# ASD2431.net
KiCad netlist of a schematic drawn in EAGLE
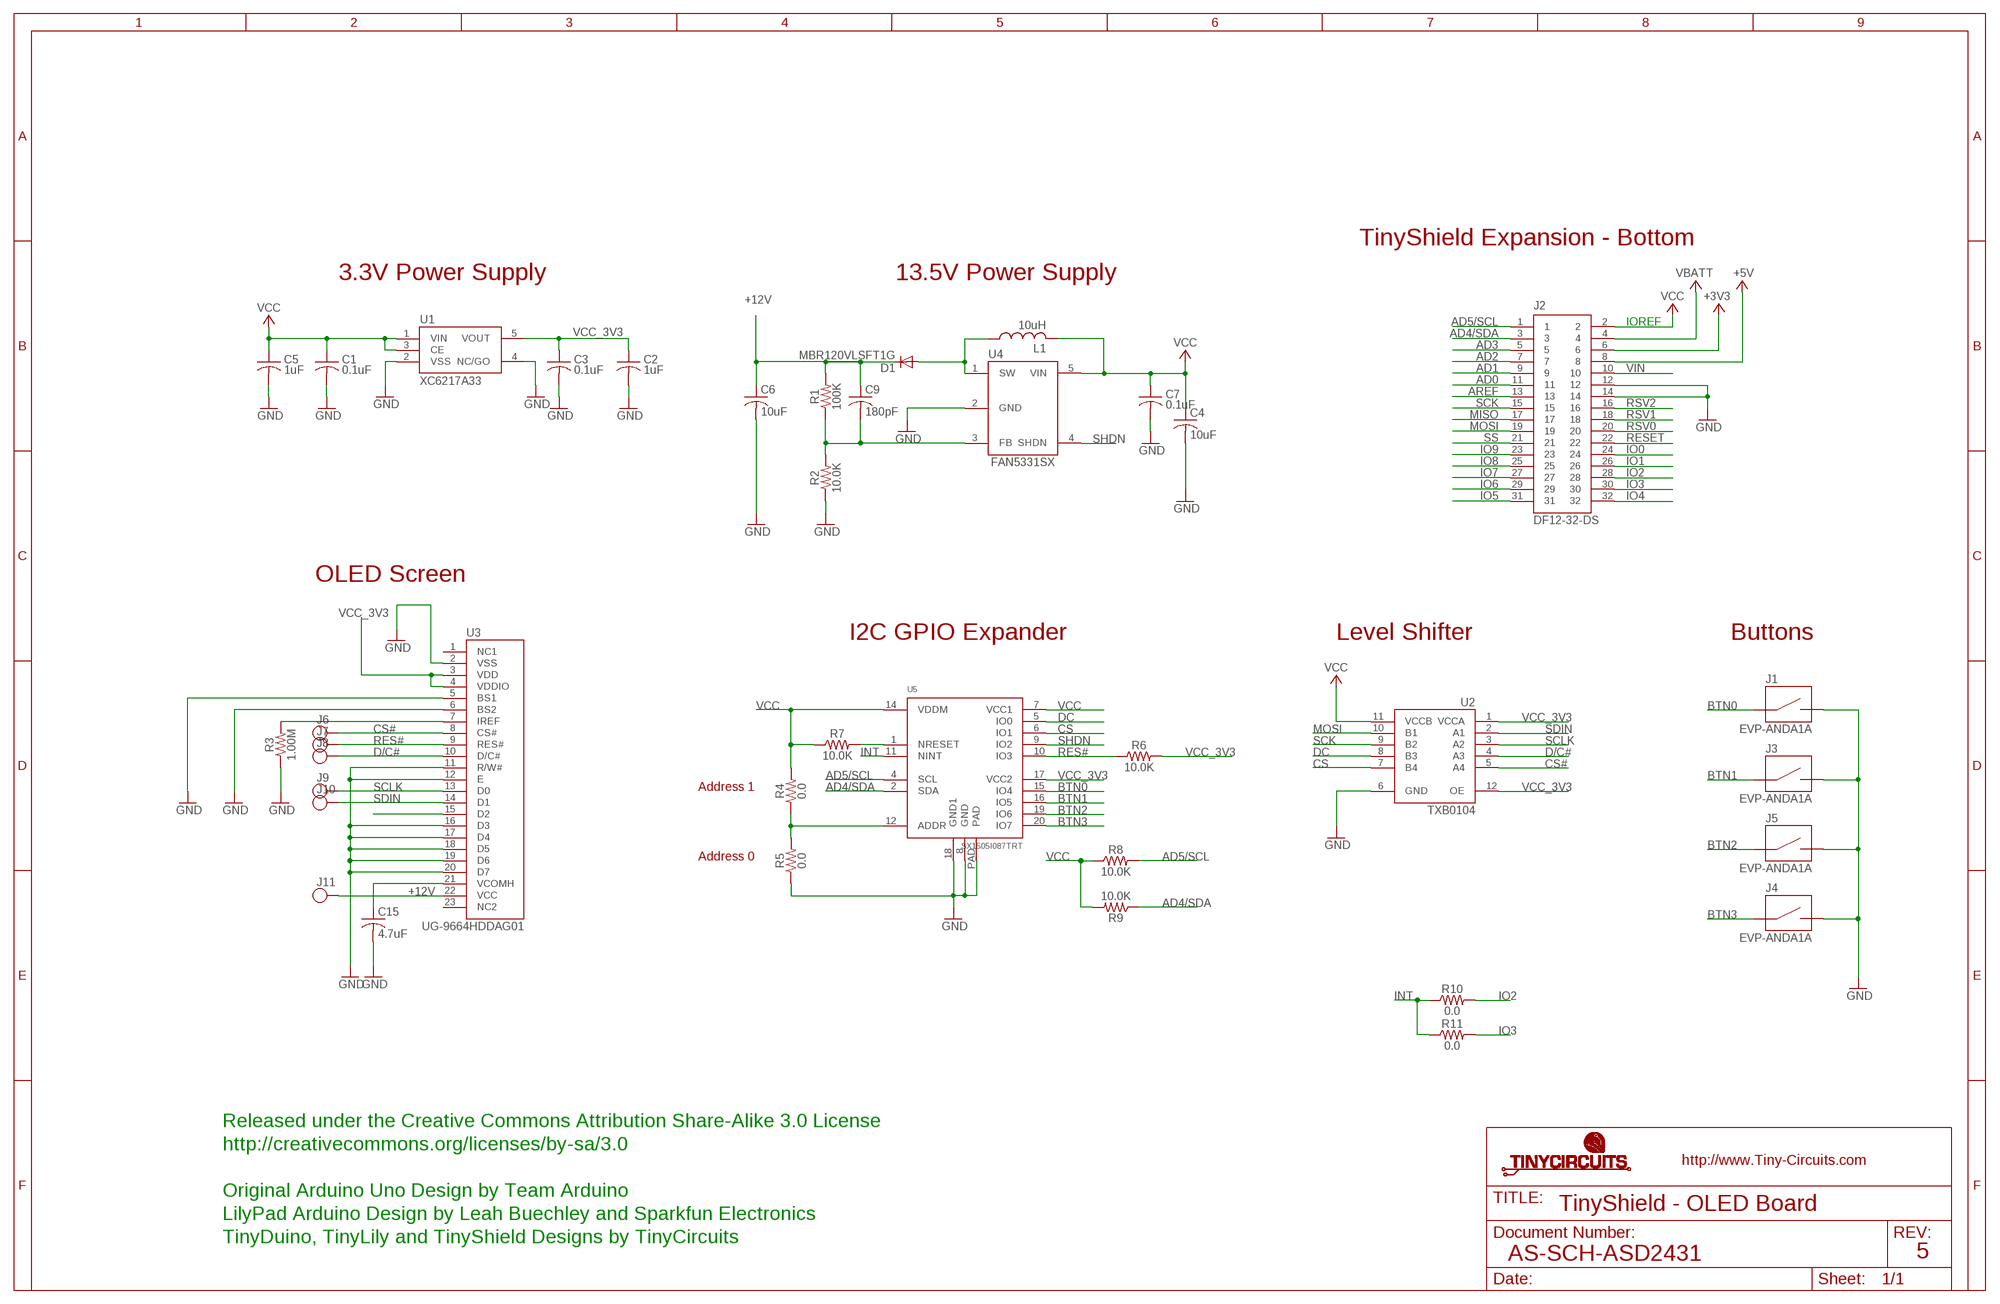
[diagram p0: schematic, sheet 1]

(export (version "E")
  (design (tool "Eeschema 10.0.6"))
  (components
    (comp (ref "C1")
      (value "0.1uF")
      (footprint "eagle-import:C0402")
      (fields (field (name "PARTNO") "AS-ITM-00008") (field (name "PARTNO_1") "AS-ITM-00008"))
      (libsource (lib "eagle-import") (part "AS-ITM-00008"))
    )
    (comp (ref "C2")
      (value "1uF")
      (footprint "eagle-import:C0402")
      (fields (field (name "PARTNO") "AS-ITM-00105") (field (name "PARTNO_1") "AS-ITM-00105"))
      (libsource (lib "eagle-import") (part "AS-ITM-00105"))
    )
    (comp (ref "C3")
      (value "0.1uF")
      (footprint "eagle-import:C0402")
      (fields (field (name "PARTNO") "AS-ITM-00008") (field (name "PARTNO_1") "AS-ITM-00008"))
      (libsource (lib "eagle-import") (part "AS-ITM-00008"))
    )
    (comp (ref "C4")
      (value "10uF")
      (footprint "eagle-import:C0805")
      (fields (field (name "PARTNO") "AS-ITM-00045") (field (name "PARTNO_1") "AS-ITM-00045"))
      (libsource (lib "eagle-import") (part "AS-ITM-00045"))
    )
    (comp (ref "C5")
      (value "1uF")
      (footprint "eagle-import:C0402")
      (fields (field (name "PARTNO") "AS-ITM-00105") (field (name "PARTNO_1") "AS-ITM-00105"))
      (libsource (lib "eagle-import") (part "AS-ITM-00105"))
    )
    (comp (ref "C6")
      (value "10uF")
      (footprint "eagle-import:C0805")
      (fields (field (name "PARTNO") "AS-ITM-00045") (field (name "PARTNO_1") "AS-ITM-00045"))
      (libsource (lib "eagle-import") (part "AS-ITM-00045"))
    )
    (comp (ref "C7")
      (value "0.1uF")
      (footprint "eagle-import:C0402")
      (fields (field (name "PARTNO") "AS-ITM-00008") (field (name "PARTNO_1") "AS-ITM-00008"))
      (libsource (lib "eagle-import") (part "AS-ITM-00008"))
    )
    (comp (ref "C9")
      (value "180pF")
      (footprint "eagle-import:0402")
      (fields (field (name "PARTNO") "AS-ITM-00243") (field (name "PARTNO_1") "AS-ITM-00243"))
      (libsource (lib "eagle-import") (part "AS-ITM-00243"))
    )
    (comp (ref "C15")
      (value "4.7uF")
      (footprint "eagle-import:1206_CAP_TANT")
      (fields (field (name "PARTNO") "AS-ITM-00232") (field (name "PARTNO_1") "AS-ITM-00232"))
      (libsource (lib "eagle-import") (part "AS-ITM-00232"))
    )
    (comp (ref "D1")
      (value "MBR120VLSFT1G")
      (footprint "eagle-import:SOD-123FL")
      (fields (field (name "PARTNO") "AS-ITM-00111"))
      (libsource (lib "eagle-import") (part "AS-ITM-00111"))
    )
    (comp (ref "J1")
      (value "EVP-ANDA1A")
      (footprint "eagle-import:PTS840GKP")
      (fields (field (name "PARTNO") "AS-ITM-00236") (field (name "PARTNO_1") "AS-ITM-00236"))
      (libsource (lib "eagle-import") (part "AS-ITM-00236"))
    )
    (comp (ref "J2")
      (value "DF12-32-DS")
      (footprint "eagle-import:DF12-32-DS")
      (fields (field (name "PARTNO") "AS-ITM-00012") (field (name "PARTNO_1") "AS-ITM-00012"))
      (libsource (lib "eagle-import") (part "AS-ITM-00012"))
    )
    (comp (ref "J3")
      (value "EVP-ANDA1A")
      (footprint "eagle-import:PTS840GKP")
      (fields (field (name "PARTNO") "AS-ITM-00236") (field (name "PARTNO_1") "AS-ITM-00236"))
      (libsource (lib "eagle-import") (part "AS-ITM-00236"))
    )
    (comp (ref "J4")
      (value "EVP-ANDA1A")
      (footprint "eagle-import:PTS840GKP")
      (fields (field (name "PARTNO") "AS-ITM-00236") (field (name "PARTNO_1") "AS-ITM-00236"))
      (libsource (lib "eagle-import") (part "AS-ITM-00236"))
    )
    (comp (ref "J5")
      (value "EVP-ANDA1A")
      (footprint "eagle-import:PTS840GKP")
      (fields (field (name "PARTNO") "AS-ITM-00236") (field (name "PARTNO_1") "AS-ITM-00236"))
      (libsource (lib "eagle-import") (part "AS-ITM-00236"))
    )
    (comp (ref "J6")
      (value "TEST_POINT")
      (footprint "eagle-import:TEST_POINT_1MM")
      (libsource (lib "eagle-import") (part "TEST_POINT"))
    )
    (comp (ref "J7")
      (value "TEST_POINT")
      (footprint "eagle-import:TEST_POINT_1MM")
      (libsource (lib "eagle-import") (part "TEST_POINT"))
    )
    (comp (ref "J8")
      (value "TEST_POINT")
      (footprint "eagle-import:TEST_POINT_1MM")
      (libsource (lib "eagle-import") (part "TEST_POINT"))
    )
    (comp (ref "J9")
      (value "TEST_POINT")
      (footprint "eagle-import:TEST_POINT_1MM")
      (libsource (lib "eagle-import") (part "TEST_POINT"))
    )
    (comp (ref "J10")
      (value "TEST_POINT")
      (footprint "eagle-import:TEST_POINT_1MM")
      (libsource (lib "eagle-import") (part "TEST_POINT"))
    )
    (comp (ref "J11")
      (value "TEST_POINT")
      (footprint "eagle-import:TEST_POINT_1MM")
      (libsource (lib "eagle-import") (part "TEST_POINT"))
    )
    (comp (ref "L1")
      (value "10uH")
      (footprint "eagle-import:R0805")
      (fields (field (name "PARTNO") "AS-ITM-00165"))
      (libsource (lib "eagle-import") (part "AS-ITM-00165"))
    )
    (comp (ref "R1")
      (value "100K")
      (footprint "eagle-import:0402")
      (fields (field (name "PARTNO") "AS-ITM-00004"))
      (libsource (lib "eagle-import") (part "AS-ITM-00004"))
    )
    (comp (ref "R2")
      (value "10.0K")
      (footprint "eagle-import:0402")
      (fields (field (name "PARTNO") "AS-ITM-00032"))
      (libsource (lib "eagle-import") (part "AS-ITM-00032"))
    )
    (comp (ref "R3")
      (value "1.00M")
      (footprint "eagle-import:0402")
      (fields (field (name "PARTNO") "AS-ITM-00005"))
      (libsource (lib "eagle-import") (part "AS-ITM-00005"))
    )
    (comp (ref "R4")
      (value "0.0")
      (footprint "eagle-import:0402")
      (fields (field (name "PARTNO") "AS-ITM-00076"))
      (libsource (lib "eagle-import") (part "AS-ITM-00076"))
    )
    (comp (ref "R5")
      (value "0.0")
      (footprint "eagle-import:0402")
      (fields (field (name "PARTNO") "AS-ITM-00076"))
      (libsource (lib "eagle-import") (part "AS-ITM-00076"))
    )
    (comp (ref "R6")
      (value "10.0K")
      (footprint "eagle-import:0402")
      (fields (field (name "PARTNO") "AS-ITM-00032"))
      (libsource (lib "eagle-import") (part "AS-ITM-00032"))
    )
    (comp (ref "R7")
      (value "10.0K")
      (footprint "eagle-import:0402")
      (fields (field (name "PARTNO") "AS-ITM-00032") (field (name "PARTNO_1") "AS-ITM-00032"))
      (libsource (lib "eagle-import") (part "AS-ITM-00032"))
    )
    (comp (ref "R8")
      (value "10.0K")
      (footprint "eagle-import:0402")
      (fields (field (name "PARTNO") "AS-ITM-00032") (field (name "PARTNO_1") "AS-ITM-00032"))
      (libsource (lib "eagle-import") (part "AS-ITM-00032"))
    )
    (comp (ref "R9")
      (value "10.0K")
      (footprint "eagle-import:0402")
      (fields (field (name "PARTNO") "AS-ITM-00032") (field (name "PARTNO_1") "AS-ITM-00032"))
      (libsource (lib "eagle-import") (part "AS-ITM-00032"))
    )
    (comp (ref "R10")
      (value "0.0")
      (footprint "eagle-import:0402")
      (fields (field (name "PARTNO") "AS-ITM-00076") (field (name "PARTNO_1") "AS-ITM-00076"))
      (libsource (lib "eagle-import") (part "AS-ITM-00076"))
    )
    (comp (ref "R11")
      (value "0.0")
      (footprint "eagle-import:0402")
      (fields (field (name "PARTNO") "AS-ITM-00076") (field (name "PARTNO_1") "AS-ITM-00076"))
      (libsource (lib "eagle-import") (part "AS-ITM-00076"))
    )
    (comp (ref "U1")
      (value "XC6217A33")
      (footprint "eagle-import:SOT-25")
      (fields (field (name "PARTNO") "AS-ITM-00249") (field (name "PARTNO_1") "AS-ITM-00249"))
      (libsource (lib "eagle-import") (part "AS-ITM-00249"))
    )
    (comp (ref "U2")
      (value "TXB0104")
      (footprint "eagle-import:UQFN-12")
      (fields (field (name "PARTNO") "AS-ITM-00048"))
      (libsource (lib "eagle-import") (part "AS-ITM-00048"))
    )
    (comp (ref "U3")
      (value "UG-9664HDDAG01")
      (footprint "eagle-import:OLED_DISPLAY")
      (fields (field (name "PARTNO") "AS-ITM-00158"))
      (libsource (lib "eagle-import") (part "AS-ITM-00158"))
    )
    (comp (ref "U4")
      (value "FAN5331SX")
      (footprint "eagle-import:SOT-23")
      (fields (field (name "PARTNO") "AS-ITM-00163"))
      (libsource (lib "eagle-import") (part "AS-ITM-00163"))
    )
    (comp (ref "U5")
      (value "SX1505I087TRT")
      (footprint "eagle-import:QFN-UT20")
      (fields (field (name "PARTNO") "AS-ITM-00203"))
      (libsource (lib "eagle-import") (part "AS-ITM-00203"))
    )
  )
  (nets
    (net (code "1") (name "+3V3") (class "Default")
      (node (ref "J2") (pin "6") (pinfunction "6_6") (pintype "bidirectional"))
    )
    (net (code "2") (name "+5V") (class "Default")
      (node (ref "J2") (pin "8") (pinfunction "8_8") (pintype "bidirectional"))
    )
    (net (code "3") (name "/+12V") (class "Default")
      (node (ref "C6") (pin "1") (pinfunction "1_1") (pintype "passive"))
      (node (ref "C9") (pin "1") (pinfunction "1_1") (pintype "passive"))
      (node (ref "D1") (pin "C") (pinfunction "C_C") (pintype "passive"))
      (node (ref "J11") (pin "P$1") (pinfunction "1_P$1") (pintype "bidirectional"))
      (node (ref "R1") (pin "2") (pinfunction "2_2") (pintype "passive"))
      (node (ref "U3") (pin "22") (pinfunction "VCC_22") (pintype "bidirectional"))
    )
    (net (code "4") (name "/AD0") (class "Default")
      (node (ref "J2") (pin "11") (pinfunction "11_11") (pintype "bidirectional"))
    )
    (net (code "5") (name "/AD1") (class "Default")
      (node (ref "J2") (pin "9") (pinfunction "9_9") (pintype "bidirectional"))
    )
    (net (code "6") (name "/AD2") (class "Default")
      (node (ref "J2") (pin "7") (pinfunction "7_7") (pintype "bidirectional"))
    )
    (net (code "7") (name "/AD3") (class "Default")
      (node (ref "J2") (pin "5") (pinfunction "5_5") (pintype "bidirectional"))
    )
    (net (code "8") (name "/AD4{slash}SDA") (class "Default")
      (node (ref "J2") (pin "3") (pinfunction "3_3") (pintype "bidirectional"))
      (node (ref "R9") (pin "1") (pinfunction "1_1") (pintype "passive"))
      (node (ref "U5") (pin "2") (pinfunction "SDA_2") (pintype "bidirectional"))
    )
    (net (code "9") (name "/AD5{slash}SCL") (class "Default")
      (node (ref "J2") (pin "1") (pinfunction "1_1") (pintype "bidirectional"))
      (node (ref "R8") (pin "2") (pinfunction "2_2") (pintype "passive"))
      (node (ref "U5") (pin "4") (pinfunction "SCL_4") (pintype "bidirectional"))
    )
    (net (code "10") (name "/AREF") (class "Default")
      (node (ref "J2") (pin "13") (pinfunction "13_13") (pintype "bidirectional"))
    )
    (net (code "11") (name "/BTN0") (class "Default")
      (node (ref "J1") (pin "1") (pinfunction "1_1") (pintype "bidirectional"))
      (node (ref "J1") (pin "2") (pinfunction "1_2") (pintype "bidirectional"))
      (node (ref "U5") (pin "15") (pinfunction "IO4_15") (pintype "bidirectional"))
    )
    (net (code "12") (name "/BTN1") (class "Default")
      (node (ref "J3") (pin "1") (pinfunction "1_1") (pintype "bidirectional"))
      (node (ref "J3") (pin "2") (pinfunction "1_2") (pintype "bidirectional"))
      (node (ref "U5") (pin "16") (pinfunction "IO5_16") (pintype "bidirectional"))
    )
    (net (code "13") (name "/BTN2") (class "Default")
      (node (ref "J5") (pin "1") (pinfunction "1_1") (pintype "bidirectional"))
      (node (ref "J5") (pin "2") (pinfunction "1_2") (pintype "bidirectional"))
      (node (ref "U5") (pin "19") (pinfunction "IO6_19") (pintype "bidirectional"))
    )
    (net (code "14") (name "/BTN3") (class "Default")
      (node (ref "J4") (pin "1") (pinfunction "1_1") (pintype "bidirectional"))
      (node (ref "J4") (pin "2") (pinfunction "1_2") (pintype "bidirectional"))
      (node (ref "U5") (pin "20") (pinfunction "IO7_20") (pintype "bidirectional"))
    )
    (net (code "15") (name "/CS") (class "Default")
      (node (ref "U2") (pin "7") (pinfunction "B4_7") (pintype "bidirectional"))
      (node (ref "U5") (pin "6") (pinfunction "IO1_6") (pintype "bidirectional"))
    )
    (net (code "16") (name "/CS#") (class "Default")
      (node (ref "J6") (pin "P$1") (pinfunction "1_P$1") (pintype "bidirectional"))
      (node (ref "U2") (pin "5") (pinfunction "A4_5") (pintype "bidirectional"))
      (node (ref "U3") (pin "8") (pinfunction "CS#_8") (pintype "bidirectional"))
    )
    (net (code "17") (name "/DC") (class "Default")
      (node (ref "U2") (pin "8") (pinfunction "B3_8") (pintype "bidirectional"))
      (node (ref "U5") (pin "5") (pinfunction "IO0_5") (pintype "bidirectional"))
    )
    (net (code "18") (name "/D{slash}C#") (class "Default")
      (node (ref "J8") (pin "P$1") (pinfunction "1_P$1") (pintype "bidirectional"))
      (node (ref "U2") (pin "4") (pinfunction "A3_4") (pintype "bidirectional"))
      (node (ref "U3") (pin "10") (pinfunction "D/C#_10") (pintype "bidirectional"))
    )
    (net (code "19") (name "/INT") (class "Default")
      (node (ref "R10") (pin "1") (pinfunction "1_1") (pintype "passive"))
      (node (ref "R11") (pin "1") (pinfunction "1_1") (pintype "passive"))
      (node (ref "U5") (pin "11") (pinfunction "NINT_11") (pintype "bidirectional"))
    )
    (net (code "20") (name "/IO0") (class "Default")
      (node (ref "J2") (pin "24") (pinfunction "24_24") (pintype "bidirectional"))
    )
    (net (code "21") (name "/IO1") (class "Default")
      (node (ref "J2") (pin "26") (pinfunction "26_26") (pintype "bidirectional"))
    )
    (net (code "22") (name "/IO2") (class "Default")
      (node (ref "J2") (pin "28") (pinfunction "28_28") (pintype "bidirectional"))
      (node (ref "R10") (pin "2") (pinfunction "2_2") (pintype "passive"))
    )
    (net (code "23") (name "/IO3") (class "Default")
      (node (ref "J2") (pin "30") (pinfunction "30_30") (pintype "bidirectional"))
      (node (ref "R11") (pin "2") (pinfunction "2_2") (pintype "passive"))
    )
    (net (code "24") (name "/IO4") (class "Default")
      (node (ref "J2") (pin "32") (pinfunction "32_32") (pintype "bidirectional"))
    )
    (net (code "25") (name "/IO5") (class "Default")
      (node (ref "J2") (pin "31") (pinfunction "31_31") (pintype "bidirectional"))
    )
    (net (code "26") (name "/IO6") (class "Default")
      (node (ref "J2") (pin "29") (pinfunction "29_29") (pintype "bidirectional"))
    )
    (net (code "27") (name "/IO7") (class "Default")
      (node (ref "J2") (pin "27") (pinfunction "27_27") (pintype "bidirectional"))
    )
    (net (code "28") (name "/IO8") (class "Default")
      (node (ref "J2") (pin "25") (pinfunction "25_25") (pintype "bidirectional"))
    )
    (net (code "29") (name "/IO9") (class "Default")
      (node (ref "J2") (pin "23") (pinfunction "23_23") (pintype "bidirectional"))
    )
    (net (code "30") (name "/MISO") (class "Default")
      (node (ref "J2") (pin "17") (pinfunction "17_17") (pintype "bidirectional"))
    )
    (net (code "31") (name "/MOSI") (class "Default")
      (node (ref "J2") (pin "19") (pinfunction "19_19") (pintype "bidirectional"))
      (node (ref "U2") (pin "10") (pinfunction "B1_10") (pintype "bidirectional"))
    )
    (net (code "32") (name "/RES#") (class "Default")
      (node (ref "J7") (pin "P$1") (pinfunction "1_P$1") (pintype "bidirectional"))
      (node (ref "R6") (pin "1") (pinfunction "1_1") (pintype "passive"))
      (node (ref "U3") (pin "9") (pinfunction "RES#_9") (pintype "bidirectional"))
      (node (ref "U5") (pin "10") (pinfunction "IO3_10") (pintype "bidirectional"))
    )
    (net (code "33") (name "/RESET") (class "Default")
      (node (ref "J2") (pin "22") (pinfunction "22_22") (pintype "bidirectional"))
    )
    (net (code "34") (name "/RSV0") (class "Default")
      (node (ref "J2") (pin "20") (pinfunction "20_20") (pintype "bidirectional"))
    )
    (net (code "35") (name "/RSV1") (class "Default")
      (node (ref "J2") (pin "18") (pinfunction "18_18") (pintype "bidirectional"))
    )
    (net (code "36") (name "/RSV2") (class "Default")
      (node (ref "J2") (pin "16") (pinfunction "16_16") (pintype "bidirectional"))
    )
    (net (code "37") (name "/SCK") (class "Default")
      (node (ref "J2") (pin "15") (pinfunction "15_15") (pintype "bidirectional"))
      (node (ref "U2") (pin "9") (pinfunction "B2_9") (pintype "bidirectional"))
    )
    (net (code "38") (name "/SCLK") (class "Default")
      (node (ref "J9") (pin "P$1") (pinfunction "1_P$1") (pintype "bidirectional"))
      (node (ref "U2") (pin "3") (pinfunction "A2_3") (pintype "bidirectional"))
      (node (ref "U3") (pin "13") (pinfunction "D0_13") (pintype "bidirectional"))
    )
    (net (code "39") (name "/SDIN") (class "Default")
      (node (ref "J10") (pin "P$1") (pinfunction "1_P$1") (pintype "bidirectional"))
      (node (ref "U2") (pin "2") (pinfunction "A1_2") (pintype "bidirectional"))
      (node (ref "U3") (pin "14") (pinfunction "D1_14") (pintype "bidirectional"))
    )
    (net (code "40") (name "/SHDN") (class "Default")
      (node (ref "U4") (pin "4") (pinfunction "SHDN_4") (pintype "bidirectional"))
      (node (ref "U5") (pin "9") (pinfunction "IO2_9") (pintype "bidirectional"))
    )
    (net (code "41") (name "/SS") (class "Default")
      (node (ref "J2") (pin "21") (pinfunction "21_21") (pintype "bidirectional"))
    )
    (net (code "42") (name "/VCC_3V3") (class "Default")
      (node (ref "C2") (pin "1") (pinfunction "1_1") (pintype "passive"))
      (node (ref "C3") (pin "1") (pinfunction "1_1") (pintype "passive"))
      (node (ref "R6") (pin "2") (pinfunction "2_2") (pintype "passive"))
      (node (ref "U1") (pin "5") (pinfunction "VOUT_5") (pintype "bidirectional"))
      (node (ref "U2") (pin "1") (pinfunction "VCCA_1") (pintype "bidirectional"))
      (node (ref "U2") (pin "12") (pinfunction "OE_12") (pintype "bidirectional"))
      (node (ref "U3") (pin "3") (pinfunction "VDD_3") (pintype "bidirectional"))
      (node (ref "U3") (pin "4") (pinfunction "VDDIO_4") (pintype "bidirectional"))
      (node (ref "U5") (pin "17") (pinfunction "VCC2_17") (pintype "bidirectional"))
    )
    (net (code "43") (name "/VIN") (class "Default")
      (node (ref "J2") (pin "10") (pinfunction "10_10") (pintype "bidirectional"))
    )
    (net (code "44") (name "GND") (class "Default")
      (node (ref "C1") (pin "2") (pinfunction "2_2") (pintype "passive"))
      (node (ref "C15") (pin "2") (pinfunction "2_2") (pintype "passive"))
      (node (ref "C2") (pin "2") (pinfunction "2_2") (pintype "passive"))
      (node (ref "C3") (pin "2") (pinfunction "2_2") (pintype "passive"))
      (node (ref "C4") (pin "2") (pinfunction "2_2") (pintype "passive"))
      (node (ref "C5") (pin "2") (pinfunction "2_2") (pintype "passive"))
      (node (ref "C6") (pin "2") (pinfunction "2_2") (pintype "passive"))
      (node (ref "C7") (pin "2") (pinfunction "2_2") (pintype "passive"))
      (node (ref "J1") (pin "3") (pinfunction "2_3") (pintype "bidirectional"))
      (node (ref "J1") (pin "4") (pinfunction "2_4") (pintype "bidirectional"))
      (node (ref "J2") (pin "12") (pinfunction "12_12") (pintype "bidirectional"))
      (node (ref "J2") (pin "14") (pinfunction "14_14") (pintype "bidirectional"))
      (node (ref "J3") (pin "3") (pinfunction "2_3") (pintype "bidirectional"))
      (node (ref "J3") (pin "4") (pinfunction "2_4") (pintype "bidirectional"))
      (node (ref "J4") (pin "3") (pinfunction "2_3") (pintype "bidirectional"))
      (node (ref "J4") (pin "4") (pinfunction "2_4") (pintype "bidirectional"))
      (node (ref "J5") (pin "3") (pinfunction "2_3") (pintype "bidirectional"))
      (node (ref "J5") (pin "4") (pinfunction "2_4") (pintype "bidirectional"))
      (node (ref "R2") (pin "1") (pinfunction "1_1") (pintype "passive"))
      (node (ref "R3") (pin "1") (pinfunction "1_1") (pintype "passive"))
      (node (ref "R5") (pin "1") (pinfunction "1_1") (pintype "passive"))
      (node (ref "U1") (pin "2") (pinfunction "VSS_2") (pintype "power_in"))
      (node (ref "U1") (pin "4") (pinfunction "NC/GO_4") (pintype "bidirectional"))
      (node (ref "U2") (pin "6") (pinfunction "GND_6") (pintype "bidirectional"))
      (node (ref "U3") (pin "11") (pinfunction "R/W#_11") (pintype "bidirectional"))
      (node (ref "U3") (pin "12") (pinfunction "E_12") (pintype "bidirectional"))
      (node (ref "U3") (pin "16") (pinfunction "D3_16") (pintype "bidirectional"))
      (node (ref "U3") (pin "17") (pinfunction "D4_17") (pintype "bidirectional"))
      (node (ref "U3") (pin "18") (pinfunction "D5_18") (pintype "bidirectional"))
      (node (ref "U3") (pin "19") (pinfunction "D6_19") (pintype "bidirectional"))
      (node (ref "U3") (pin "2") (pinfunction "VSS_2") (pintype "bidirectional"))
      (node (ref "U3") (pin "20") (pinfunction "D7_20") (pintype "bidirectional"))
      (node (ref "U3") (pin "5") (pinfunction "BS1_5") (pintype "bidirectional"))
      (node (ref "U3") (pin "6") (pinfunction "BS2_6") (pintype "bidirectional"))
      (node (ref "U4") (pin "2") (pinfunction "GND_2") (pintype "bidirectional"))
      (node (ref "U5") (pin "18") (pinfunction "GND1_18") (pintype "bidirectional"))
      (node (ref "U5") (pin "8") (pinfunction "GND_8") (pintype "bidirectional"))
      (node (ref "U5") (pin "PAD") (pinfunction "PAD_PAD") (pintype "bidirectional"))
    )
    (net (code "45") (name "Net-(U3-IREF)") (class "Default")
      (node (ref "R3") (pin "2") (pinfunction "2_2") (pintype "passive"))
      (node (ref "U3") (pin "7") (pinfunction "IREF_7") (pintype "bidirectional"))
    )
    (net (code "46") (name "Net-(U3-VCOMH)") (class "Default")
      (node (ref "C15") (pin "1") (pinfunction "1_1") (pintype "passive"))
      (node (ref "U3") (pin "21") (pinfunction "VCOMH_21") (pintype "bidirectional"))
    )
    (net (code "47") (name "Net-(U4-FB)") (class "Default")
      (node (ref "C9") (pin "2") (pinfunction "2_2") (pintype "passive"))
      (node (ref "R1") (pin "1") (pinfunction "1_1") (pintype "passive"))
      (node (ref "R2") (pin "2") (pinfunction "2_2") (pintype "passive"))
      (node (ref "U4") (pin "3") (pinfunction "FB_3") (pintype "bidirectional"))
    )
    (net (code "48") (name "Net-(U4-SW)") (class "Default")
      (node (ref "D1") (pin "A") (pinfunction "A_A") (pintype "passive"))
      (node (ref "L1") (pin "1") (pinfunction "1_1") (pintype "passive"))
      (node (ref "U4") (pin "1") (pinfunction "SW_1") (pintype "bidirectional"))
    )
    (net (code "49") (name "Net-(U5-ADDR)") (class "Default")
      (node (ref "R4") (pin "1") (pinfunction "1_1") (pintype "passive"))
      (node (ref "R5") (pin "2") (pinfunction "2_2") (pintype "passive"))
      (node (ref "U5") (pin "12") (pinfunction "ADDR_12") (pintype "bidirectional"))
    )
    (net (code "50") (name "Net-(U5-NRESET)") (class "Default")
      (node (ref "R7") (pin "2") (pinfunction "2_2") (pintype "passive"))
      (node (ref "U5") (pin "1") (pinfunction "NRESET_1") (pintype "bidirectional"))
    )
    (net (code "51") (name "VBATT") (class "Default")
      (node (ref "J2") (pin "4") (pinfunction "4_4") (pintype "bidirectional"))
    )
    (net (code "52") (name "VCC") (class "Default")
      (node (ref "C1") (pin "1") (pinfunction "1_1") (pintype "passive"))
      (node (ref "C4") (pin "1") (pinfunction "1_1") (pintype "passive"))
      (node (ref "C5") (pin "1") (pinfunction "1_1") (pintype "passive"))
      (node (ref "C7") (pin "1") (pinfunction "1_1") (pintype "passive"))
      (node (ref "J2") (pin "2") (pinfunction "2_2") (pintype "bidirectional"))
      (node (ref "L1") (pin "2") (pinfunction "2_2") (pintype "passive"))
      (node (ref "R4") (pin "2") (pinfunction "2_2") (pintype "passive"))
      (node (ref "R7") (pin "1") (pinfunction "1_1") (pintype "passive"))
      (node (ref "R8") (pin "1") (pinfunction "1_1") (pintype "passive"))
      (node (ref "R9") (pin "2") (pinfunction "2_2") (pintype "passive"))
      (node (ref "U1") (pin "1") (pinfunction "VIN_1") (pintype "bidirectional"))
      (node (ref "U1") (pin "3") (pinfunction "CE_3") (pintype "bidirectional"))
      (node (ref "U2") (pin "11") (pinfunction "VCCB_11") (pintype "bidirectional"))
      (node (ref "U4") (pin "5") (pinfunction "VIN_5") (pintype "bidirectional"))
      (node (ref "U5") (pin "14") (pinfunction "VDDM_14") (pintype "bidirectional"))
      (node (ref "U5") (pin "7") (pinfunction "VCC1_7") (pintype "bidirectional"))
    )
    (net (code "53") (name "unconnected-(U3-D2-Pad15)") (class "Default")
      (node (ref "U3") (pin "15") (pinfunction "D2_15") (pintype "bidirectional"))
    )
    (net (code "54") (name "unconnected-(U3-NC1-Pad1)") (class "Default")
      (node (ref "U3") (pin "1") (pinfunction "NC1_1") (pintype "bidirectional"))
    )
    (net (code "55") (name "unconnected-(U3-NC2-Pad23)") (class "Default")
      (node (ref "U3") (pin "23") (pinfunction "NC2_23") (pintype "bidirectional"))
    )
  )
)
